# master.net
KiCad netlist of a schematic drawn in EAGLE
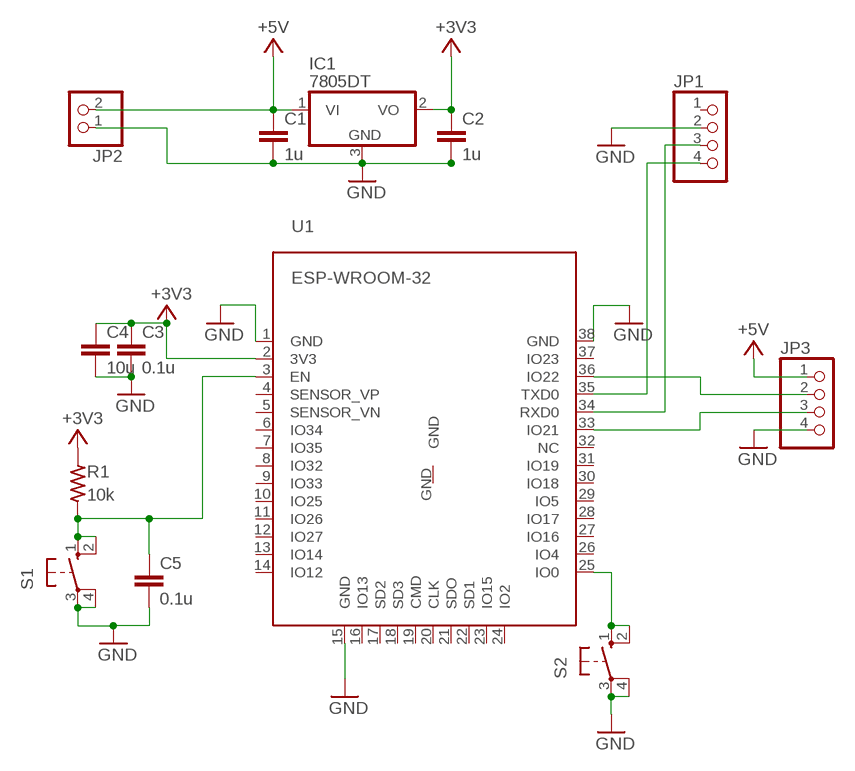
[diagram p0: schematic, sheet 1]

(export (version "E")
  (design (tool "Eeschema 10.0.6"))
  (components
    (comp (ref "C1")
      (value "1u")
      (footprint "eagle-import:C1608")
      (libsource (lib "eagle-import") (part "C-EUC1608"))
    )
    (comp (ref "C2")
      (value "1u")
      (footprint "eagle-import:C1608")
      (libsource (lib "eagle-import") (part "C-EUC1608"))
    )
    (comp (ref "C3")
      (value "0.1u")
      (footprint "eagle-import:C1608")
      (libsource (lib "eagle-import") (part "C-EUC1608"))
    )
    (comp (ref "C4")
      (value "10u")
      (footprint "eagle-import:C1608")
      (libsource (lib "eagle-import") (part "C-EUC1608"))
    )
    (comp (ref "C5")
      (value "0.1u")
      (footprint "eagle-import:C1608")
      (libsource (lib "eagle-import") (part "C-EUC1608"))
    )
    (comp (ref "IC1")
      (value "7805DT")
      (footprint "eagle-import:TO252")
      (libsource (lib "eagle-import") (part "78DT05"))
    )
    (comp (ref "JP1")
      (value "PINHD-1X4")
      (footprint "eagle-import:1X04")
      (libsource (lib "eagle-import") (part "PINHD-1X4"))
    )
    (comp (ref "JP2")
      (value "PINHD-1X2")
      (footprint "eagle-import:1X02")
      (libsource (lib "eagle-import") (part "PINHD-1X2"))
    )
    (comp (ref "JP3")
      (value "PINHD-1X4")
      (footprint "eagle-import:1X04")
      (libsource (lib "eagle-import") (part "PINHD-1X4"))
    )
    (comp (ref "R1")
      (value "10k")
      (footprint "eagle-import:SMD1608")
      (libsource (lib "eagle-import") (part "RESISTOR-US1608"))
    )
    (comp (ref "S1")
      (value "10-XX")
      (footprint "eagle-import:B3F-10XX")
      (fields (field (name "MPN") "B3F-1000"))
      (libsource (lib "eagle-import") (part "10-XX"))
    )
    (comp (ref "S2")
      (value "10-XX")
      (footprint "eagle-import:B3F-10XX")
      (fields (field (name "MPN") "B3F-1000"))
      (libsource (lib "eagle-import") (part "10-XX"))
    )
    (comp (ref "U1")
      (value "ESP-WROOM-32")
      (footprint "eagle-import:ESP-WROOM-32")
      (libsource (lib "eagle-import") (part "ESP-WROOM-32"))
    )
  )
  (nets
    (net (code "1") (name "+3V3") (class "Default")
      (node (ref "C2") (pin "1") (pinfunction "1_1") (pintype "passive"))
      (node (ref "C3") (pin "1") (pinfunction "1_1") (pintype "passive"))
      (node (ref "C4") (pin "1") (pinfunction "1_1") (pintype "passive"))
      (node (ref "IC1") (pin "2") (pinfunction "VO_2") (pintype "passive"))
      (node (ref "R1") (pin "1") (pinfunction "1_1") (pintype "passive"))
      (node (ref "U1") (pin "2") (pinfunction "3V3_2") (pintype "bidirectional"))
    )
    (net (code "2") (name "+5V") (class "Default")
      (node (ref "C1") (pin "1") (pinfunction "1_1") (pintype "passive"))
      (node (ref "IC1") (pin "1") (pinfunction "VI_1") (pintype "input"))
      (node (ref "JP2") (pin "2") (pinfunction "2_2") (pintype "passive"))
      (node (ref "JP3") (pin "1") (pinfunction "1_1") (pintype "passive"))
    )
    (net (code "3") (name "GND") (class "Default")
      (node (ref "C1") (pin "2") (pinfunction "2_2") (pintype "passive"))
      (node (ref "C2") (pin "2") (pinfunction "2_2") (pintype "passive"))
      (node (ref "C3") (pin "2") (pinfunction "2_2") (pintype "passive"))
      (node (ref "C4") (pin "2") (pinfunction "2_2") (pintype "passive"))
      (node (ref "C5") (pin "2") (pinfunction "2_2") (pintype "passive"))
      (node (ref "IC1") (pin "3") (pinfunction "GND_3") (pintype "passive"))
      (node (ref "JP1") (pin "2") (pinfunction "2_2") (pintype "passive"))
      (node (ref "JP2") (pin "1") (pinfunction "1_1") (pintype "passive"))
      (node (ref "JP3") (pin "4") (pinfunction "4_4") (pintype "passive"))
      (node (ref "S1") (pin "3") (pinfunction "P_3") (pintype "passive"))
      (node (ref "S1") (pin "4") (pinfunction "P1_4") (pintype "passive"))
      (node (ref "S2") (pin "3") (pinfunction "P_3") (pintype "passive"))
      (node (ref "S2") (pin "4") (pinfunction "P1_4") (pintype "passive"))
      (node (ref "U1") (pin "1") (pinfunction "GND_1") (pintype "bidirectional"))
      (node (ref "U1") (pin "15") (pinfunction "GND_15") (pintype "bidirectional"))
      (node (ref "U1") (pin "38") (pinfunction "GND_38") (pintype "bidirectional"))
    )
    (net (code "4") (name "Net-(S1-S)") (class "Default")
      (node (ref "C5") (pin "1") (pinfunction "1_1") (pintype "passive"))
      (node (ref "R1") (pin "2") (pinfunction "2_2") (pintype "passive"))
      (node (ref "S1") (pin "1") (pinfunction "S_1") (pintype "passive"))
      (node (ref "S1") (pin "2") (pinfunction "S1_2") (pintype "passive"))
      (node (ref "U1") (pin "3") (pinfunction "EN_3") (pintype "bidirectional"))
    )
    (net (code "5") (name "Net-(S2-S)") (class "Default")
      (node (ref "S2") (pin "1") (pinfunction "S_1") (pintype "passive"))
      (node (ref "S2") (pin "2") (pinfunction "S1_2") (pintype "passive"))
      (node (ref "U1") (pin "25") (pinfunction "IO0_25") (pintype "bidirectional"))
    )
    (net (code "6") (name "Net-(U1-IO21)") (class "Default")
      (node (ref "JP3") (pin "3") (pinfunction "3_3") (pintype "passive"))
      (node (ref "U1") (pin "33") (pinfunction "IO21_33") (pintype "bidirectional"))
    )
    (net (code "7") (name "Net-(U1-IO22)") (class "Default")
      (node (ref "JP3") (pin "2") (pinfunction "2_2") (pintype "passive"))
      (node (ref "U1") (pin "36") (pinfunction "IO22_36") (pintype "bidirectional"))
    )
    (net (code "8") (name "Net-(U1-RXD0)") (class "Default")
      (node (ref "JP1") (pin "3") (pinfunction "3_3") (pintype "passive"))
      (node (ref "U1") (pin "34") (pinfunction "RXD0_34") (pintype "bidirectional"))
    )
    (net (code "9") (name "Net-(U1-TXD0)") (class "Default")
      (node (ref "JP1") (pin "4") (pinfunction "4_4") (pintype "passive"))
      (node (ref "U1") (pin "35") (pinfunction "TXD0_35") (pintype "bidirectional"))
    )
    (net (code "10") (name "unconnected-(JP1-Pad1)") (class "Default")
      (node (ref "JP1") (pin "1") (pinfunction "1_1") (pintype "passive"))
    )
    (net (code "11") (name "unconnected-(U1-CLK-Pad20)") (class "Default")
      (node (ref "U1") (pin "20") (pinfunction "CLK_20") (pintype "bidirectional"))
    )
    (net (code "12") (name "unconnected-(U1-CMD-Pad19)") (class "Default")
      (node (ref "U1") (pin "19") (pinfunction "CMD_19") (pintype "bidirectional"))
    )
    (net (code "13") (name "unconnected-(U1-IO2-Pad24)") (class "Default")
      (node (ref "U1") (pin "24") (pinfunction "IO2_24") (pintype "bidirectional"))
    )
    (net (code "14") (name "unconnected-(U1-IO4-Pad26)") (class "Default")
      (node (ref "U1") (pin "26") (pinfunction "IO4_26") (pintype "bidirectional"))
    )
    (net (code "15") (name "unconnected-(U1-IO5-Pad29)") (class "Default")
      (node (ref "U1") (pin "29") (pinfunction "IO5_29") (pintype "bidirectional"))
    )
    (net (code "16") (name "unconnected-(U1-IO12-Pad14)") (class "Default")
      (node (ref "U1") (pin "14") (pinfunction "IO12_14") (pintype "bidirectional"))
    )
    (net (code "17") (name "unconnected-(U1-IO13-Pad16)") (class "Default")
      (node (ref "U1") (pin "16") (pinfunction "IO13_16") (pintype "bidirectional"))
    )
    (net (code "18") (name "unconnected-(U1-IO14-Pad13)") (class "Default")
      (node (ref "U1") (pin "13") (pinfunction "IO14_13") (pintype "bidirectional"))
    )
    (net (code "19") (name "unconnected-(U1-IO15-Pad23)") (class "Default")
      (node (ref "U1") (pin "23") (pinfunction "IO15_23") (pintype "bidirectional"))
    )
    (net (code "20") (name "unconnected-(U1-IO16-Pad27)") (class "Default")
      (node (ref "U1") (pin "27") (pinfunction "IO16_27") (pintype "bidirectional"))
    )
    (net (code "21") (name "unconnected-(U1-IO17-Pad28)") (class "Default")
      (node (ref "U1") (pin "28") (pinfunction "IO17_28") (pintype "bidirectional"))
    )
    (net (code "22") (name "unconnected-(U1-IO18-Pad30)") (class "Default")
      (node (ref "U1") (pin "30") (pinfunction "IO18_30") (pintype "bidirectional"))
    )
    (net (code "23") (name "unconnected-(U1-IO19-Pad31)") (class "Default")
      (node (ref "U1") (pin "31") (pinfunction "IO19_31") (pintype "bidirectional"))
    )
    (net (code "24") (name "unconnected-(U1-IO23-Pad37)") (class "Default")
      (node (ref "U1") (pin "37") (pinfunction "IO23_37") (pintype "bidirectional"))
    )
    (net (code "25") (name "unconnected-(U1-IO25-Pad10)") (class "Default")
      (node (ref "U1") (pin "10") (pinfunction "IO25_10") (pintype "bidirectional"))
    )
    (net (code "26") (name "unconnected-(U1-IO26-Pad11)") (class "Default")
      (node (ref "U1") (pin "11") (pinfunction "IO26_11") (pintype "bidirectional"))
    )
    (net (code "27") (name "unconnected-(U1-IO27-Pad12)") (class "Default")
      (node (ref "U1") (pin "12") (pinfunction "IO27_12") (pintype "bidirectional"))
    )
    (net (code "28") (name "unconnected-(U1-IO32-Pad8)") (class "Default")
      (node (ref "U1") (pin "8") (pinfunction "IO32_8") (pintype "bidirectional"))
    )
    (net (code "29") (name "unconnected-(U1-IO33-Pad9)") (class "Default")
      (node (ref "U1") (pin "9") (pinfunction "IO33_9") (pintype "bidirectional"))
    )
    (net (code "30") (name "unconnected-(U1-IO34-Pad6)") (class "Default")
      (node (ref "U1") (pin "6") (pinfunction "IO34_6") (pintype "bidirectional"))
    )
    (net (code "31") (name "unconnected-(U1-IO35-Pad7)") (class "Default")
      (node (ref "U1") (pin "7") (pinfunction "IO35_7") (pintype "bidirectional"))
    )
    (net (code "32") (name "unconnected-(U1-NC-Pad32)") (class "Default")
      (node (ref "U1") (pin "32") (pinfunction "NC_32") (pintype "bidirectional"))
    )
    (net (code "33") (name "unconnected-(U1-PadGND)") (class "Default")
      (node (ref "U1") (pin "GND") (pinfunction "GND_GND") (pintype "bidirectional"))
    )
    (net (code "34") (name "unconnected-(U1-SD1-Pad22)") (class "Default")
      (node (ref "U1") (pin "22") (pinfunction "SD1_22") (pintype "bidirectional"))
    )
    (net (code "35") (name "unconnected-(U1-SD2-Pad17)") (class "Default")
      (node (ref "U1") (pin "17") (pinfunction "SD2_17") (pintype "bidirectional"))
    )
    (net (code "36") (name "unconnected-(U1-SD3-Pad18)") (class "Default")
      (node (ref "U1") (pin "18") (pinfunction "SD3_18") (pintype "bidirectional"))
    )
    (net (code "37") (name "unconnected-(U1-SDO-Pad21)") (class "Default")
      (node (ref "U1") (pin "21") (pinfunction "SDO_21") (pintype "bidirectional"))
    )
    (net (code "38") (name "unconnected-(U1-SENSOR_VN-Pad5)") (class "Default")
      (node (ref "U1") (pin "5") (pinfunction "SENSOR_VN_5") (pintype "bidirectional"))
    )
    (net (code "39") (name "unconnected-(U1-SENSOR_VP-Pad4)") (class "Default")
      (node (ref "U1") (pin "4") (pinfunction "SENSOR_VP_4") (pintype "bidirectional"))
    )
  )
)
